# power.net
KiCad netlist of a schematic drawn in Altium Designer
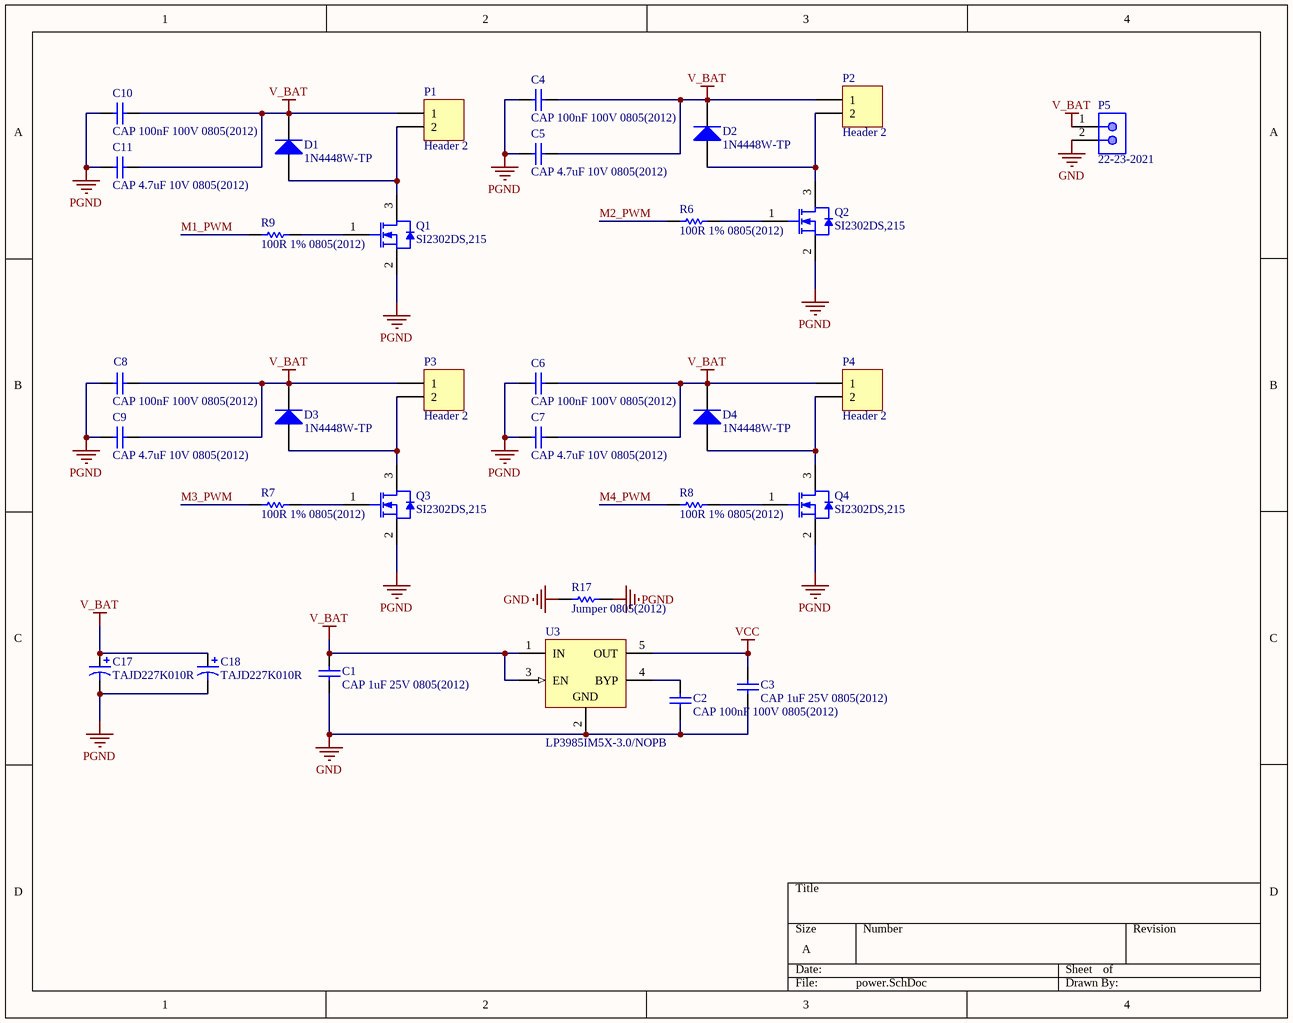
[diagram p0: power.SchDoc]

(export (version "E")
  (design (tool "Eeschema 10.0.6"))
  (components
    (comp (ref "C1")
      (value "CAP 1uF 25V 0805(2012)")
      (footprint "CAPC0805(2012)100_M")
      (description "CAP 1uF 25V ±10% 0805 (2012 Metric) Thickness 1mm SMD")
      (fields (field (name "TOLERANCE") "Â±10%"))
      (libsource (lib "Altium Content Vault") (part "CMP-1036-04754-1"))
    )
    (comp (ref "C2")
      (value "CAP 100nF 100V 0805(2012)")
      (footprint "CAPC0805(2012)145_N")
      (description "CAP 100nF 100V ±20% 0805 (2012 Metric) Thickness 1.45mm SMD")
      (fields (field (name "TOLERANCE") "Â±20%"))
      (libsource (lib "Altium Content Vault") (part "CMP-1036-04431-1"))
    )
    (comp (ref "C3")
      (value "CAP 1uF 25V 0805(2012)")
      (footprint "CAPC0805(2012)100_M")
      (description "CAP 1uF 25V ±10% 0805 (2012 Metric) Thickness 1mm SMD")
      (fields (field (name "TOLERANCE") "Â±10%"))
      (libsource (lib "Altium Content Vault") (part "CMP-1036-04754-1"))
    )
    (comp (ref "C4")
      (value "CAP 100nF 100V 0805(2012)")
      (footprint "CAPC0805(2012)145_N")
      (description "CAP 100nF 100V ±20% 0805 (2012 Metric) Thickness 1.45mm SMD")
      (fields (field (name "TOLERANCE") "Â±20%"))
      (libsource (lib "Altium Content Vault") (part "CMP-1036-04431-1"))
    )
    (comp (ref "C5")
      (value "CAP 4.7uF 10V 0805(2012)")
      (footprint "CAPC0805(2012)155_L")
      (description "CAP 4.7uF 10V ±10% 0805 (2012 Metric) Thickness 1.55mm SMD")
      (fields (field (name "TOLERANCE") "Â±10%"))
      (libsource (lib "Altium Content Vault") (part "CAP"))
    )
    (comp (ref "C6")
      (value "CAP 100nF 100V 0805(2012)")
      (footprint "CAPC0805(2012)145_N")
      (description "CAP 100nF 100V ±20% 0805 (2012 Metric) Thickness 1.45mm SMD")
      (fields (field (name "TOLERANCE") "Â±20%"))
      (libsource (lib "Altium Content Vault") (part "CMP-1036-04431-1"))
    )
    (comp (ref "C7")
      (value "CAP 4.7uF 10V 0805(2012)")
      (footprint "CAPC0805(2012)155_L")
      (description "CAP 4.7uF 10V ±10% 0805 (2012 Metric) Thickness 1.55mm SMD")
      (fields (field (name "TOLERANCE") "Â±10%"))
      (libsource (lib "Altium Content Vault") (part "CAP"))
    )
    (comp (ref "C8")
      (value "CAP 100nF 100V 0805(2012)")
      (footprint "CAPC0805(2012)145_N")
      (description "CAP 100nF 100V ±20% 0805 (2012 Metric) Thickness 1.45mm SMD")
      (fields (field (name "TOLERANCE") "Â±20%"))
      (libsource (lib "Altium Content Vault") (part "CMP-1036-04431-1"))
    )
    (comp (ref "C9")
      (value "CAP 4.7uF 10V 0805(2012)")
      (footprint "CAPC0805(2012)155_L")
      (description "CAP 4.7uF 10V ±10% 0805 (2012 Metric) Thickness 1.55mm SMD")
      (fields (field (name "TOLERANCE") "Â±10%"))
      (libsource (lib "Altium Content Vault") (part "CAP"))
    )
    (comp (ref "C10")
      (value "CAP 100nF 100V 0805(2012)")
      (footprint "CAPC0805(2012)145_N")
      (description "CAP 100nF 100V ±20% 0805 (2012 Metric) Thickness 1.45mm SMD")
      (fields (field (name "TOLERANCE") "Â±20%"))
      (libsource (lib "Altium Content Vault") (part "CMP-1036-04431-1"))
    )
    (comp (ref "C11")
      (value "CAP 4.7uF 10V 0805(2012)")
      (footprint "CAPC0805(2012)155_L")
      (description "CAP 4.7uF 10V ±10% 0805 (2012 Metric) Thickness 1.55mm SMD")
      (fields (field (name "TOLERANCE") "Â±10%"))
      (libsource (lib "Altium Content Vault") (part "CAP"))
    )
    (comp (ref "C17")
      (value "TAJD227K010R")
      (footprint "AVX-CAPC7343_V")
      (description "Capacitor, Tantalum, 220uF 10% 10V MCCT-D (7343-31)")
      (fields (field (name "TOLERANCE") "10%") (field (name "MANUFACTURER") "AVX"))
      (libsource (lib "Altium Content Vault") (part "CMP-0279-00002-2"))
    )
    (comp (ref "C18")
      (value "TAJD227K010R")
      (footprint "AVX-CAPC7343_V")
      (description "Capacitor, Tantalum, 220uF 10% 10V MCCT-D (7343-31)")
      (fields (field (name "TOLERANCE") "10%") (field (name "MANUFACTURER") "AVX"))
      (libsource (lib "Altium Content Vault") (part "CMP-0279-00002-2"))
    )
    (comp (ref "D1")
      (value "1N4448W-TP")
      (footprint "MCC-SOD123_V")
      (description "Switching Diode, 500 mW, 100 V, -55 to 150 degC, SOD123, RoHS, Tape and Reel")
      (fields (field (name "MANUFACTURER") "Micro Commercial Components"))
      (libsource (lib "Altium Content Vault") (part "CMP-0862-00001-1"))
    )
    (comp (ref "D2")
      (value "1N4448W-TP")
      (footprint "MCC-SOD123_V")
      (description "Switching Diode, 500 mW, 100 V, -55 to 150 degC, SOD123, RoHS, Tape and Reel")
      (fields (field (name "MANUFACTURER") "Micro Commercial Components"))
      (libsource (lib "Altium Content Vault") (part "CMP-0862-00001-1"))
    )
    (comp (ref "D3")
      (value "1N4448W-TP")
      (footprint "MCC-SOD123_V")
      (description "Switching Diode, 500 mW, 100 V, -55 to 150 degC, SOD123, RoHS, Tape and Reel")
      (fields (field (name "MANUFACTURER") "Micro Commercial Components"))
      (libsource (lib "Altium Content Vault") (part "CMP-0862-00001-1"))
    )
    (comp (ref "D4")
      (value "1N4448W-TP")
      (footprint "MCC-SOD123_V")
      (description "Switching Diode, 500 mW, 100 V, -55 to 150 degC, SOD123, RoHS, Tape and Reel")
      (fields (field (name "MANUFACTURER") "Micro Commercial Components"))
      (libsource (lib "Altium Content Vault") (part "CMP-0862-00001-1"))
    )
    (comp (ref "P1")
      (value "Header 2")
      (footprint "HDR1X2")
      (description "Header, 2-Pin")
      (fields (field (name "PUBLISHER") "Altium Limited"))
      (libsource (lib "Miscellaneous Connectors") (part "Header 2"))
    )
    (comp (ref "P2")
      (value "Header 2")
      (footprint "HDR1X2")
      (description "Header, 2-Pin")
      (fields (field (name "PUBLISHER") "Altium Limited"))
      (libsource (lib "Miscellaneous Connectors") (part "Header 2"))
    )
    (comp (ref "P3")
      (value "Header 2")
      (footprint "HDR1X2")
      (description "Header, 2-Pin")
      (fields (field (name "PUBLISHER") "Altium Limited"))
      (libsource (lib "Miscellaneous Connectors") (part "Header 2"))
    )
    (comp (ref "P4")
      (value "Header 2")
      (footprint "HDR1X2")
      (description "Header, 2-Pin")
      (fields (field (name "PUBLISHER") "Altium Limited"))
      (libsource (lib "Miscellaneous Connectors") (part "Header 2"))
    )
    (comp (ref "P5")
      (value "22-23-2021")
      (footprint "MOLX-22-23-2021_V")
      (libsource (lib "Altium Content Vault") (part "CMP-1704-00001-3"))
    )
    (comp (ref "Q1")
      (value "SI2302DS,215")
      (footprint "NXP-SOT23_N")
      (description "N-Channel Enhancement Mode Field-Effect Transistor, 20 V, 2.5 A, 3-Pin SOT23, Tape and Reel")
      (fields (field (name "MANUFACTURER") "NXP Semiconductors"))
      (libsource (lib "Altium Content Vault") (part "CMP-1258-00133-1"))
    )
    (comp (ref "Q2")
      (value "SI2302DS,215")
      (footprint "NXP-SOT23_N")
      (description "N-Channel Enhancement Mode Field-Effect Transistor, 20 V, 2.5 A, 3-Pin SOT23, Tape and Reel")
      (fields (field (name "MANUFACTURER") "NXP Semiconductors"))
      (libsource (lib "Altium Content Vault") (part "CMP-1258-00133-1"))
    )
    (comp (ref "Q3")
      (value "SI2302DS,215")
      (footprint "NXP-SOT23_N")
      (description "N-Channel Enhancement Mode Field-Effect Transistor, 20 V, 2.5 A, 3-Pin SOT23, Tape and Reel")
      (fields (field (name "MANUFACTURER") "NXP Semiconductors"))
      (libsource (lib "Altium Content Vault") (part "CMP-1258-00133-1"))
    )
    (comp (ref "Q4")
      (value "SI2302DS,215")
      (footprint "NXP-SOT23_N")
      (description "N-Channel Enhancement Mode Field-Effect Transistor, 20 V, 2.5 A, 3-Pin SOT23, Tape and Reel")
      (fields (field (name "MANUFACTURER") "NXP Semiconductors"))
      (libsource (lib "Altium Content Vault") (part "CMP-1258-00133-1"))
    )
    (comp (ref "R6")
      (value "100R 1% 0805(2012)")
      (footprint "RESC0805(2012)_L")
      (description "100R 0.125W 1% 0805 (2012 Metric)  SMD")
      (fields (field (name "POWER") "0.125 W") (field (name "TOLERANCE") "1 %"))
      (libsource (lib "Altium Content Vault") (part "CMP-1013-00397-1"))
    )
    (comp (ref "R7")
      (value "100R 1% 0805(2012)")
      (footprint "RESC0805(2012)_L")
      (description "100R 0.125W 1% 0805 (2012 Metric)  SMD")
      (fields (field (name "POWER") "0.125 W") (field (name "TOLERANCE") "1 %"))
      (libsource (lib "Altium Content Vault") (part "CMP-1013-00397-1"))
    )
    (comp (ref "R8")
      (value "100R 1% 0805(2012)")
      (footprint "RESC0805(2012)_L")
      (description "100R 0.125W 1% 0805 (2012 Metric)  SMD")
      (fields (field (name "POWER") "0.125 W") (field (name "TOLERANCE") "1 %"))
      (libsource (lib "Altium Content Vault") (part "CMP-1013-00397-1"))
    )
    (comp (ref "R9")
      (value "100R 1% 0805(2012)")
      (footprint "RESC0805(2012)_L")
      (description "100R 0.125W 1% 0805 (2012 Metric)  SMD")
      (fields (field (name "POWER") "0.125 W") (field (name "TOLERANCE") "1 %"))
      (libsource (lib "Altium Content Vault") (part "CMP-1013-00397-1"))
    )
    (comp (ref "R17")
      (value "Jumper 0805(2012)")
      (footprint "RESC0805(2012)_N")
      (description "Jumper 0805 (2012 Metric)")
      (fields (field (name "TOLERANCE") "None"))
      (libsource (lib "Altium Content Vault") (part "RES"))
    )
    (comp (ref "U3")
      (value "LP3985IM5X-3.0/NOPB")
      (footprint "MF05A_L")
      (description "Micropower, 150mA Low-Noise Ultra Low-Dropout CMOS Voltage Regulator, 5-pin SOT-23, Pb-Free")
      (fields (field (name "MANUFACTURER") "National Semiconductor"))
      (libsource (lib "Altium Content Vault") (part "CMP-0062-01849-2"))
    )
  )
  (nets
    (net (code "1") (name "/M1_PWM") (class "Default")
      (node (ref "R9") (pin "1") (pinfunction "1_1") (pintype "passive"))
    )
    (net (code "2") (name "/M2_PWM") (class "Default")
      (node (ref "R6") (pin "1") (pinfunction "1_1") (pintype "passive"))
    )
    (net (code "3") (name "/M3_PWM") (class "Default")
      (node (ref "R7") (pin "1") (pinfunction "1_1") (pintype "passive"))
    )
    (net (code "4") (name "/M4_PWM") (class "Default")
      (node (ref "R8") (pin "1") (pinfunction "1_1") (pintype "passive"))
    )
    (net (code "5") (name "GND") (class "Default")
      (node (ref "C1") (pin "1") (pinfunction "1_1") (pintype "passive"))
      (node (ref "C2") (pin "1") (pinfunction "1_1") (pintype "passive"))
      (node (ref "C3") (pin "1") (pinfunction "1_1") (pintype "passive"))
      (node (ref "P5") (pin "2") (pinfunction "2_2") (pintype "passive"))
      (node (ref "R17") (pin "1") (pinfunction "1_1") (pintype "passive"))
      (node (ref "U3") (pin "2") (pinfunction "GND_2") (pintype "power_in"))
    )
    (net (code "6") (name "Net-(D1-A)") (class "Default")
      (node (ref "D1") (pin "1") (pinfunction "A_1") (pintype "passive"))
      (node (ref "P1") (pin "2") (pinfunction "2_2") (pintype "passive"))
      (node (ref "Q1") (pin "3") (pinfunction "D_3") (pintype "passive"))
    )
    (net (code "7") (name "Net-(D2-A)") (class "Default")
      (node (ref "D2") (pin "1") (pinfunction "A_1") (pintype "passive"))
      (node (ref "P2") (pin "2") (pinfunction "2_2") (pintype "passive"))
      (node (ref "Q2") (pin "3") (pinfunction "D_3") (pintype "passive"))
    )
    (net (code "8") (name "Net-(D3-A)") (class "Default")
      (node (ref "D3") (pin "1") (pinfunction "A_1") (pintype "passive"))
      (node (ref "P3") (pin "2") (pinfunction "2_2") (pintype "passive"))
      (node (ref "Q3") (pin "3") (pinfunction "D_3") (pintype "passive"))
    )
    (net (code "9") (name "Net-(D4-A)") (class "Default")
      (node (ref "D4") (pin "1") (pinfunction "A_1") (pintype "passive"))
      (node (ref "P4") (pin "2") (pinfunction "2_2") (pintype "passive"))
      (node (ref "Q4") (pin "3") (pinfunction "D_3") (pintype "passive"))
    )
    (net (code "10") (name "Net-(Q1-G)") (class "Default")
      (node (ref "Q1") (pin "1") (pinfunction "G_1") (pintype "passive"))
      (node (ref "R9") (pin "2") (pinfunction "2_2") (pintype "passive"))
    )
    (net (code "11") (name "Net-(Q2-G)") (class "Default")
      (node (ref "Q2") (pin "1") (pinfunction "G_1") (pintype "passive"))
      (node (ref "R6") (pin "2") (pinfunction "2_2") (pintype "passive"))
    )
    (net (code "12") (name "Net-(Q3-G)") (class "Default")
      (node (ref "Q3") (pin "1") (pinfunction "G_1") (pintype "passive"))
      (node (ref "R7") (pin "2") (pinfunction "2_2") (pintype "passive"))
    )
    (net (code "13") (name "Net-(Q4-G)") (class "Default")
      (node (ref "Q4") (pin "1") (pinfunction "G_1") (pintype "passive"))
      (node (ref "R8") (pin "2") (pinfunction "2_2") (pintype "passive"))
    )
    (net (code "14") (name "Net-(U3-BYP)") (class "Default")
      (node (ref "C2") (pin "2") (pinfunction "2_2") (pintype "passive"))
      (node (ref "U3") (pin "4") (pinfunction "BYP_4") (pintype "passive"))
    )
    (net (code "15") (name "PGND") (class "Default")
      (node (ref "C10") (pin "1") (pinfunction "1_1") (pintype "passive"))
      (node (ref "C11") (pin "1") (pinfunction "1_1") (pintype "passive"))
      (node (ref "C17") (pin "2") (pinfunction "2_2") (pintype "passive"))
      (node (ref "C18") (pin "2") (pinfunction "2_2") (pintype "passive"))
      (node (ref "C4") (pin "1") (pinfunction "1_1") (pintype "passive"))
      (node (ref "C5") (pin "1") (pinfunction "1_1") (pintype "passive"))
      (node (ref "C6") (pin "1") (pinfunction "1_1") (pintype "passive"))
      (node (ref "C7") (pin "1") (pinfunction "1_1") (pintype "passive"))
      (node (ref "C8") (pin "1") (pinfunction "1_1") (pintype "passive"))
      (node (ref "C9") (pin "1") (pinfunction "1_1") (pintype "passive"))
      (node (ref "Q1") (pin "2") (pinfunction "S_2") (pintype "passive"))
      (node (ref "Q2") (pin "2") (pinfunction "S_2") (pintype "passive"))
      (node (ref "Q3") (pin "2") (pinfunction "S_2") (pintype "passive"))
      (node (ref "Q4") (pin "2") (pinfunction "S_2") (pintype "passive"))
      (node (ref "R17") (pin "2") (pinfunction "2_2") (pintype "passive"))
    )
    (net (code "16") (name "VCC") (class "Default")
      (node (ref "C3") (pin "2") (pinfunction "2_2") (pintype "passive"))
      (node (ref "U3") (pin "5") (pinfunction "OUT_5") (pintype "power_in"))
    )
    (net (code "17") (name "V_BAT") (class "Default")
      (node (ref "C1") (pin "2") (pinfunction "2_2") (pintype "passive"))
      (node (ref "C10") (pin "2") (pinfunction "2_2") (pintype "passive"))
      (node (ref "C11") (pin "2") (pinfunction "2_2") (pintype "passive"))
      (node (ref "C17") (pin "1") (pinfunction "1_1") (pintype "passive"))
      (node (ref "C18") (pin "1") (pinfunction "1_1") (pintype "passive"))
      (node (ref "C4") (pin "2") (pinfunction "2_2") (pintype "passive"))
      (node (ref "C5") (pin "2") (pinfunction "2_2") (pintype "passive"))
      (node (ref "C6") (pin "2") (pinfunction "2_2") (pintype "passive"))
      (node (ref "C7") (pin "2") (pinfunction "2_2") (pintype "passive"))
      (node (ref "C8") (pin "2") (pinfunction "2_2") (pintype "passive"))
      (node (ref "C9") (pin "2") (pinfunction "2_2") (pintype "passive"))
      (node (ref "D1") (pin "2") (pinfunction "K_2") (pintype "passive"))
      (node (ref "D2") (pin "2") (pinfunction "K_2") (pintype "passive"))
      (node (ref "D3") (pin "2") (pinfunction "K_2") (pintype "passive"))
      (node (ref "D4") (pin "2") (pinfunction "K_2") (pintype "passive"))
      (node (ref "P1") (pin "1") (pinfunction "1_1") (pintype "passive"))
      (node (ref "P2") (pin "1") (pinfunction "1_1") (pintype "passive"))
      (node (ref "P3") (pin "1") (pinfunction "1_1") (pintype "passive"))
      (node (ref "P4") (pin "1") (pinfunction "1_1") (pintype "passive"))
      (node (ref "P5") (pin "1") (pinfunction "1_1") (pintype "passive"))
      (node (ref "U3") (pin "1") (pinfunction "IN_1") (pintype "power_in"))
      (node (ref "U3") (pin "3") (pinfunction "EN_3") (pintype "input"))
    )
  )
)
